# POW.net
KiCad netlist of a schematic drawn in Altium Designer
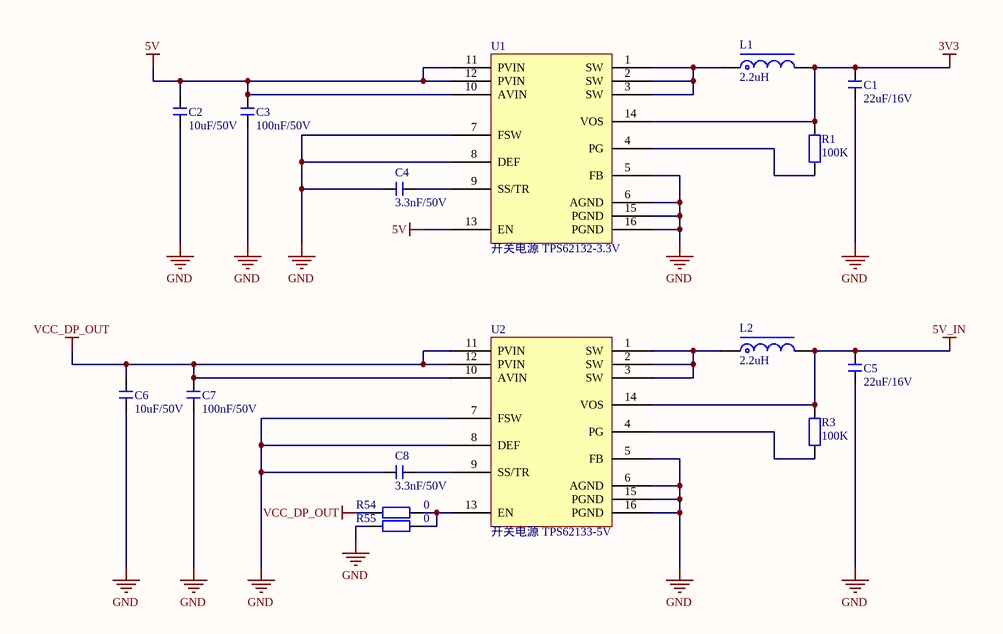
[diagram p0: POW.SchDoc]

(export (version "E")
  (design (tool "Eeschema 10.0.6"))
  (components
    (comp (ref "C1")
      (value "22uF/16V")
      (footprint "C 0805_L")
      (description "贴片电容")
      (libsource (lib "3.1   - 电阻-电容-电感") (part "C"))
    )
    (comp (ref "C2")
      (value "10uF/50V")
      (footprint "C 0805_L")
      (description "贴片电容")
      (libsource (lib "3.1   - 电阻-电容-电感") (part "C"))
    )
    (comp (ref "C3")
      (value "100nF/50V")
      (footprint "C 0603_L")
      (description "贴片电容")
      (libsource (lib "3.1   - 电阻-电容-电感") (part "C"))
    )
    (comp (ref "C4")
      (value "3.3nF/50V")
      (footprint "C 0402_L")
      (description "贴片电容")
      (libsource (lib "3.1   - 电阻-电容-电感") (part "C"))
    )
    (comp (ref "C5")
      (value "22uF/16V")
      (footprint "C 0805_L")
      (description "贴片电容")
      (libsource (lib "3.1   - 电阻-电容-电感") (part "C"))
    )
    (comp (ref "C6")
      (value "10uF/50V")
      (footprint "C 0805_L")
      (description "贴片电容")
      (libsource (lib "3.1   - 电阻-电容-电感") (part "C"))
    )
    (comp (ref "C7")
      (value "100nF/50V")
      (footprint "C 0603_L")
      (description "贴片电容")
      (libsource (lib "3.1   - 电阻-电容-电感") (part "C"))
    )
    (comp (ref "C8")
      (value "3.3nF/50V")
      (footprint "C 0402_L")
      (description "贴片电容")
      (libsource (lib "3.1   - 电阻-电容-电感") (part "C"))
    )
    (comp (ref "L1")
      (value "2.2uH")
      (footprint "电感XFL4020")
      (description "XFL4020-222MEB")
      (libsource (lib "3.1   - 电阻-电容-电感") (part "L-CD"))
    )
    (comp (ref "L2")
      (value "2.2uH")
      (footprint "电感XFL4020")
      (description "XFL4020-222MEB")
      (libsource (lib "3.1   - 电阻-电容-电感") (part "L-CD"))
    )
    (comp (ref "R1")
      (value "100K")
      (footprint "R 0402_L")
      (description "贴片电阻 0402 1%")
      (libsource (lib "3.1   - 电阻-电容-电感") (part "R"))
    )
    (comp (ref "R3")
      (value "100K")
      (footprint "R 0402_L")
      (description "贴片电阻 0402 1%")
      (libsource (lib "3.1   - 电阻-电容-电感") (part "R"))
    )
    (comp (ref "R54")
      (value "0")
      (footprint "R 0402_L")
      (description "贴片电阻")
      (libsource (lib "3.1   - 电阻-电容-电感") (part "R"))
    )
    (comp (ref "R55")
      (value "0")
      (footprint "R 0402_L")
      (description "贴片电阻")
      (libsource (lib "3.1   - 电阻-电容-电感") (part "R"))
    )
    (comp (ref "U1")
      (value "开关电源 TPS62132-3.3V")
      (footprint "QFN16")
      (libsource (lib "Schlib1") (part "开关电源 TPS62133"))
    )
    (comp (ref "U2")
      (value "开关电源 TPS62133-5V")
      (footprint "QFN16")
      (libsource (lib "Schlib1") (part "开关电源 TPS62133"))
    )
  )
  (nets
    (net (code "1") (name "3V3") (class "Default")
      (node (ref "C1") (pin "1") (pinfunction "1_1") (pintype "passive"))
      (node (ref "L1") (pin "2") (pinfunction "2_2") (pintype "passive"))
      (node (ref "R1") (pin "2") (pinfunction "2_2") (pintype "passive"))
      (node (ref "U1") (pin "14") (pinfunction "VOS_14") (pintype "passive"))
    )
    (net (code "2") (name "5V") (class "Default")
      (node (ref "C2") (pin "2") (pinfunction "2_2") (pintype "passive"))
      (node (ref "C3") (pin "2") (pinfunction "2_2") (pintype "passive"))
      (node (ref "U1") (pin "10") (pinfunction "AVIN_10") (pintype "passive"))
      (node (ref "U1") (pin "11") (pinfunction "PVIN_11") (pintype "passive"))
      (node (ref "U1") (pin "12") (pinfunction "PVIN_12") (pintype "passive"))
      (node (ref "U1") (pin "13") (pinfunction "EN_13") (pintype "passive"))
    )
    (net (code "3") (name "5V_IN") (class "Default")
      (node (ref "C5") (pin "1") (pinfunction "1_1") (pintype "passive"))
      (node (ref "L2") (pin "2") (pinfunction "2_2") (pintype "passive"))
      (node (ref "R3") (pin "1") (pinfunction "1_1") (pintype "passive"))
      (node (ref "U2") (pin "14") (pinfunction "VOS_14") (pintype "passive"))
    )
    (net (code "4") (name "GND") (class "Default")
      (node (ref "C1") (pin "2") (pinfunction "2_2") (pintype "passive"))
      (node (ref "C2") (pin "1") (pinfunction "1_1") (pintype "passive"))
      (node (ref "C3") (pin "1") (pinfunction "1_1") (pintype "passive"))
      (node (ref "C4") (pin "1") (pinfunction "1_1") (pintype "passive"))
      (node (ref "C5") (pin "2") (pinfunction "2_2") (pintype "passive"))
      (node (ref "C6") (pin "1") (pinfunction "1_1") (pintype "passive"))
      (node (ref "C7") (pin "1") (pinfunction "1_1") (pintype "passive"))
      (node (ref "C8") (pin "1") (pinfunction "1_1") (pintype "passive"))
      (node (ref "R55") (pin "1") (pinfunction "1_1") (pintype "passive"))
      (node (ref "U1") (pin "15") (pinfunction "PGND_15") (pintype "passive"))
      (node (ref "U1") (pin "16") (pinfunction "PGND_16") (pintype "passive"))
      (node (ref "U1") (pin "5") (pinfunction "FB_5") (pintype "passive"))
      (node (ref "U1") (pin "6") (pinfunction "AGND_6") (pintype "passive"))
      (node (ref "U1") (pin "7") (pinfunction "FSW_7") (pintype "passive"))
      (node (ref "U1") (pin "8") (pinfunction "DEF_8") (pintype "passive"))
      (node (ref "U2") (pin "15") (pinfunction "PGND_15") (pintype "passive"))
      (node (ref "U2") (pin "16") (pinfunction "PGND_16") (pintype "passive"))
      (node (ref "U2") (pin "5") (pinfunction "FB_5") (pintype "passive"))
      (node (ref "U2") (pin "6") (pinfunction "AGND_6") (pintype "passive"))
      (node (ref "U2") (pin "7") (pinfunction "FSW_7") (pintype "passive"))
      (node (ref "U2") (pin "8") (pinfunction "DEF_8") (pintype "passive"))
    )
    (net (code "5") (name "Net-(L1-Pad1)") (class "Default")
      (node (ref "L1") (pin "1") (pinfunction "1_1") (pintype "passive"))
      (node (ref "U1") (pin "1") (pinfunction "SW_1") (pintype "passive"))
      (node (ref "U1") (pin "2") (pinfunction "SW_2") (pintype "passive"))
      (node (ref "U1") (pin "3") (pinfunction "SW_3") (pintype "passive"))
    )
    (net (code "6") (name "Net-(L2-Pad1)") (class "Default")
      (node (ref "L2") (pin "1") (pinfunction "1_1") (pintype "passive"))
      (node (ref "U2") (pin "1") (pinfunction "SW_1") (pintype "passive"))
      (node (ref "U2") (pin "2") (pinfunction "SW_2") (pintype "passive"))
      (node (ref "U2") (pin "3") (pinfunction "SW_3") (pintype "passive"))
    )
    (net (code "7") (name "Net-(U1-PG)") (class "Default")
      (node (ref "R1") (pin "1") (pinfunction "1_1") (pintype "passive"))
      (node (ref "U1") (pin "4") (pinfunction "PG_4") (pintype "passive"))
    )
    (net (code "8") (name "Net-(U1-SS{slash}TR)") (class "Default")
      (node (ref "C4") (pin "2") (pinfunction "2_2") (pintype "passive"))
      (node (ref "U1") (pin "9") (pinfunction "SS/TR_9") (pintype "passive"))
    )
    (net (code "9") (name "Net-(U2-EN)") (class "Default")
      (node (ref "R54") (pin "2") (pinfunction "2_2") (pintype "passive"))
      (node (ref "R55") (pin "2") (pinfunction "2_2") (pintype "passive"))
      (node (ref "U2") (pin "13") (pinfunction "EN_13") (pintype "passive"))
    )
    (net (code "10") (name "Net-(U2-PG)") (class "Default")
      (node (ref "R3") (pin "2") (pinfunction "2_2") (pintype "passive"))
      (node (ref "U2") (pin "4") (pinfunction "PG_4") (pintype "passive"))
    )
    (net (code "11") (name "Net-(U2-SS{slash}TR)") (class "Default")
      (node (ref "C8") (pin "2") (pinfunction "2_2") (pintype "passive"))
      (node (ref "U2") (pin "9") (pinfunction "SS/TR_9") (pintype "passive"))
    )
    (net (code "12") (name "VCC_DP_OUT") (class "Default")
      (node (ref "C6") (pin "2") (pinfunction "2_2") (pintype "passive"))
      (node (ref "C7") (pin "2") (pinfunction "2_2") (pintype "passive"))
      (node (ref "R54") (pin "1") (pinfunction "1_1") (pintype "passive"))
      (node (ref "U2") (pin "10") (pinfunction "AVIN_10") (pintype "passive"))
      (node (ref "U2") (pin "11") (pinfunction "PVIN_11") (pintype "passive"))
      (node (ref "U2") (pin "12") (pinfunction "PVIN_12") (pintype "passive"))
    )
  )
)
